# MonitorWizard-Logger.net
KiCad netlist of a schematic drawn in EAGLE
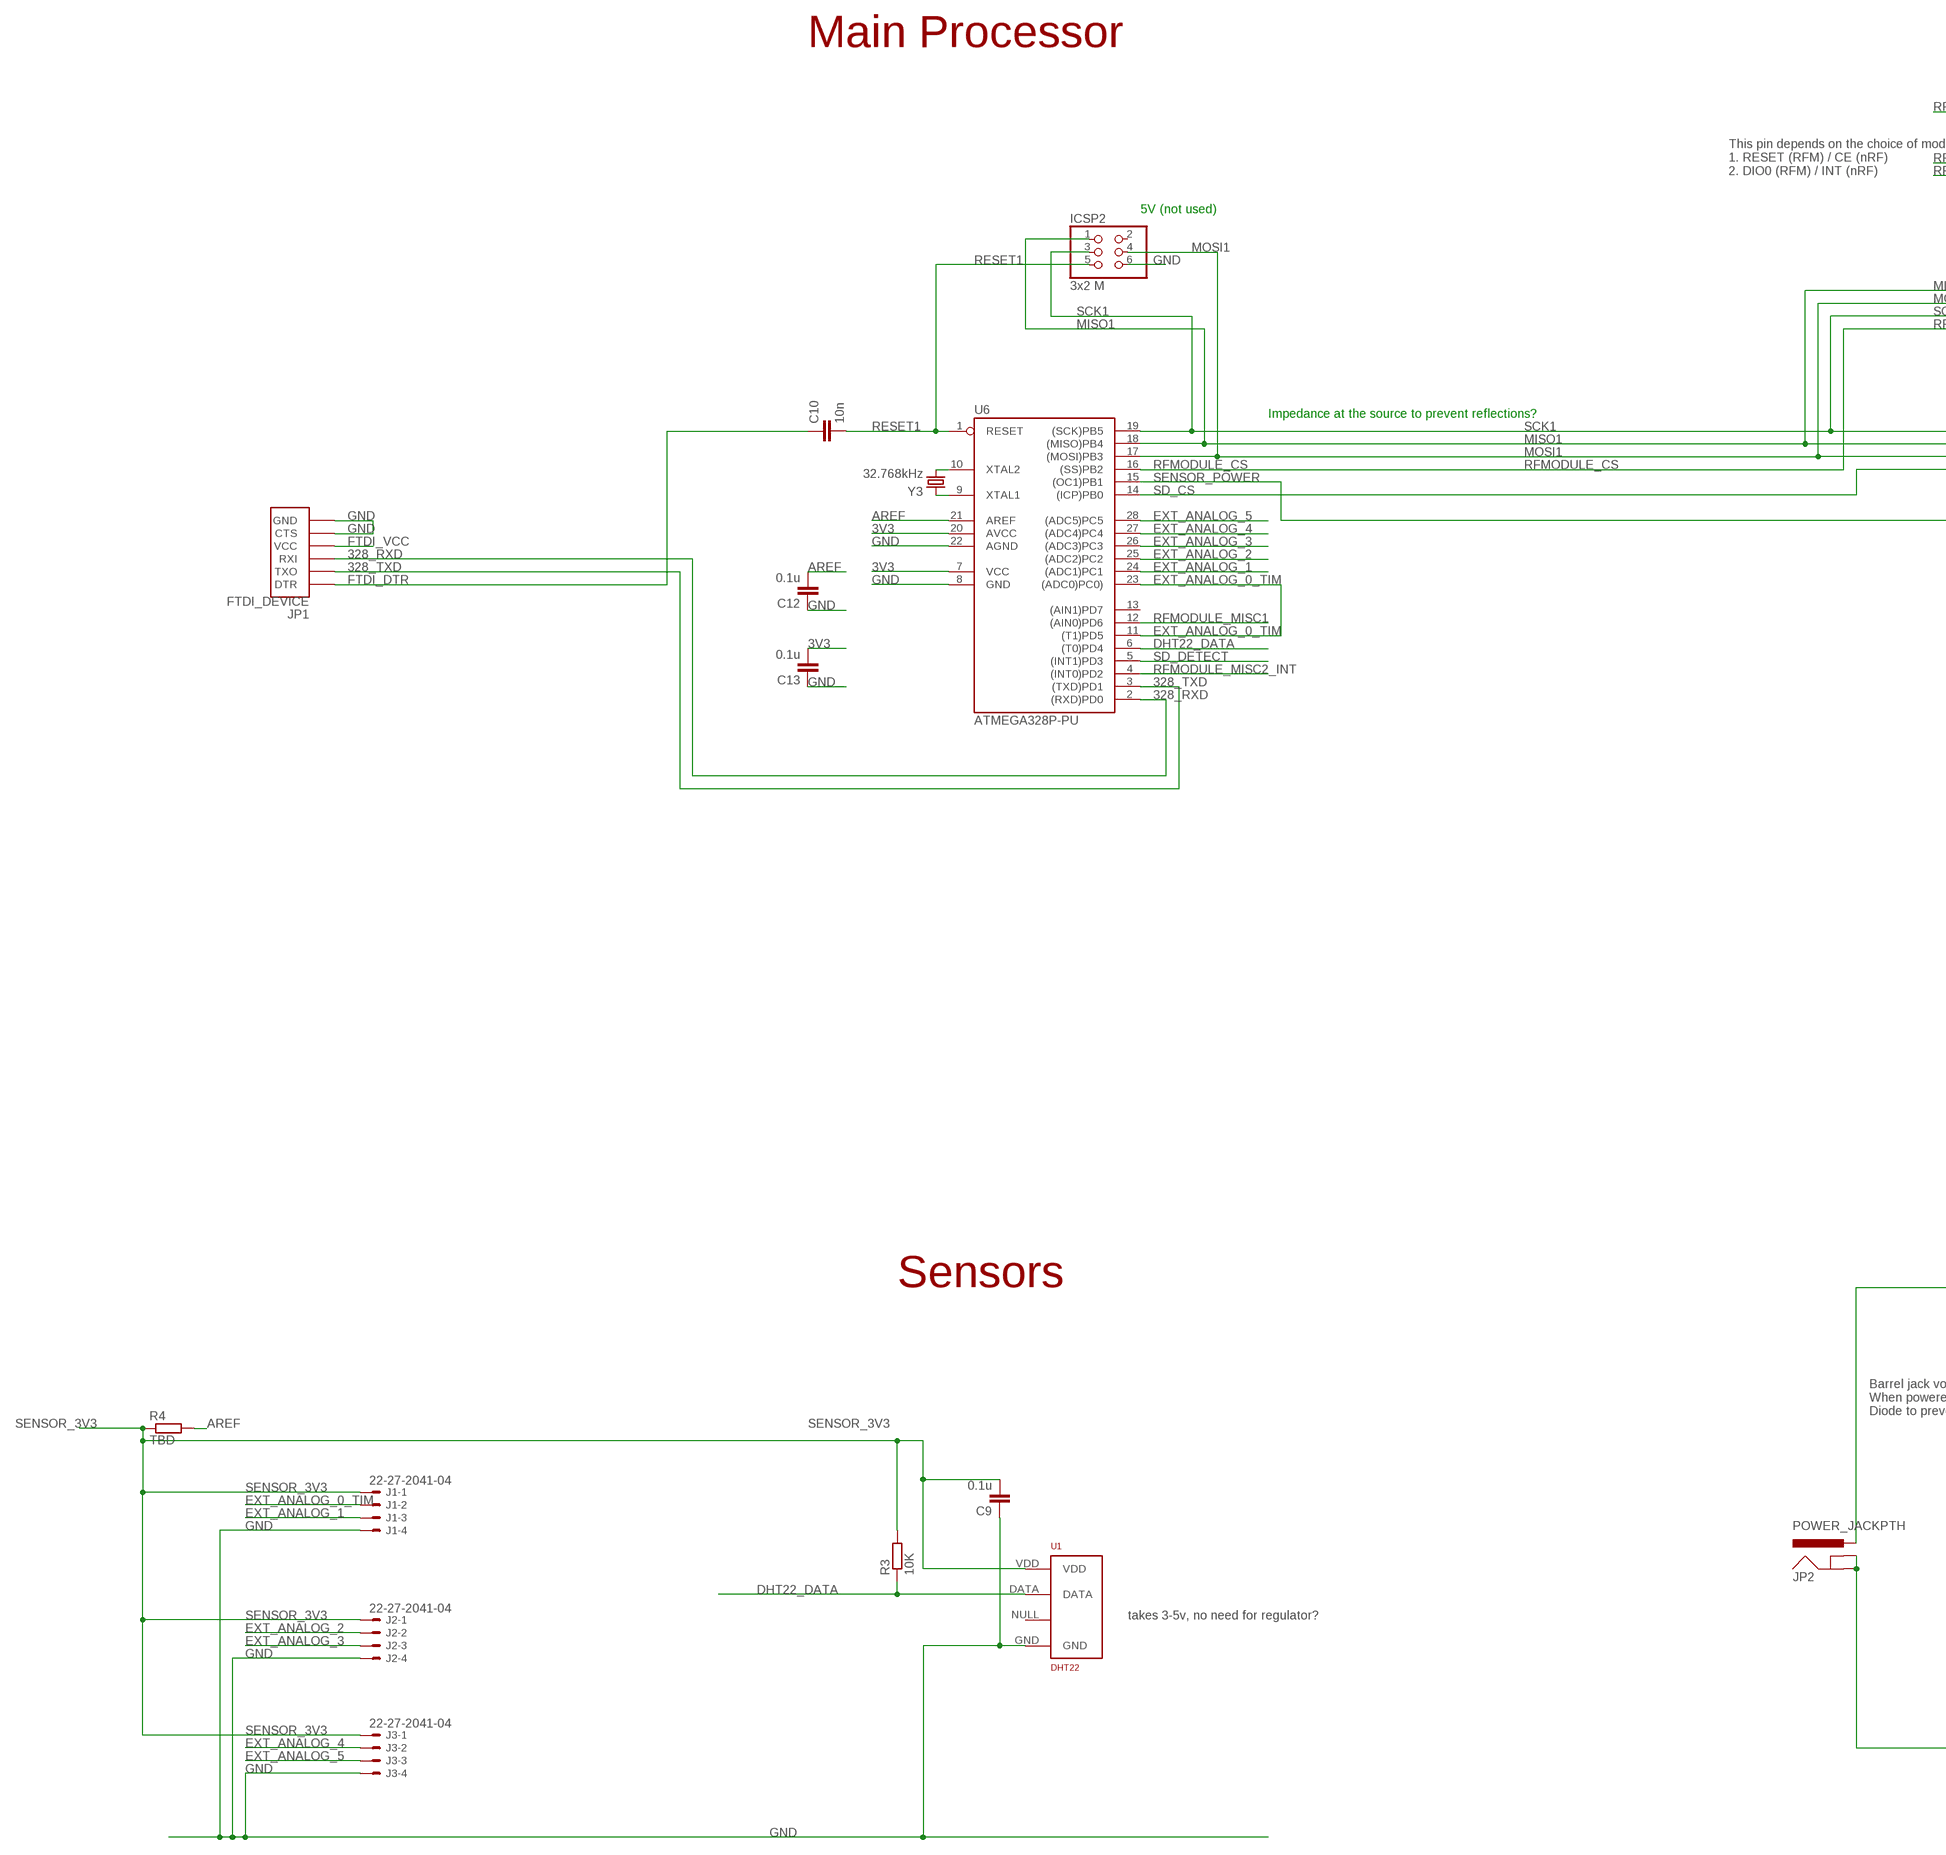
[diagram p0: schematic, sheet 1, part 1 of 2]
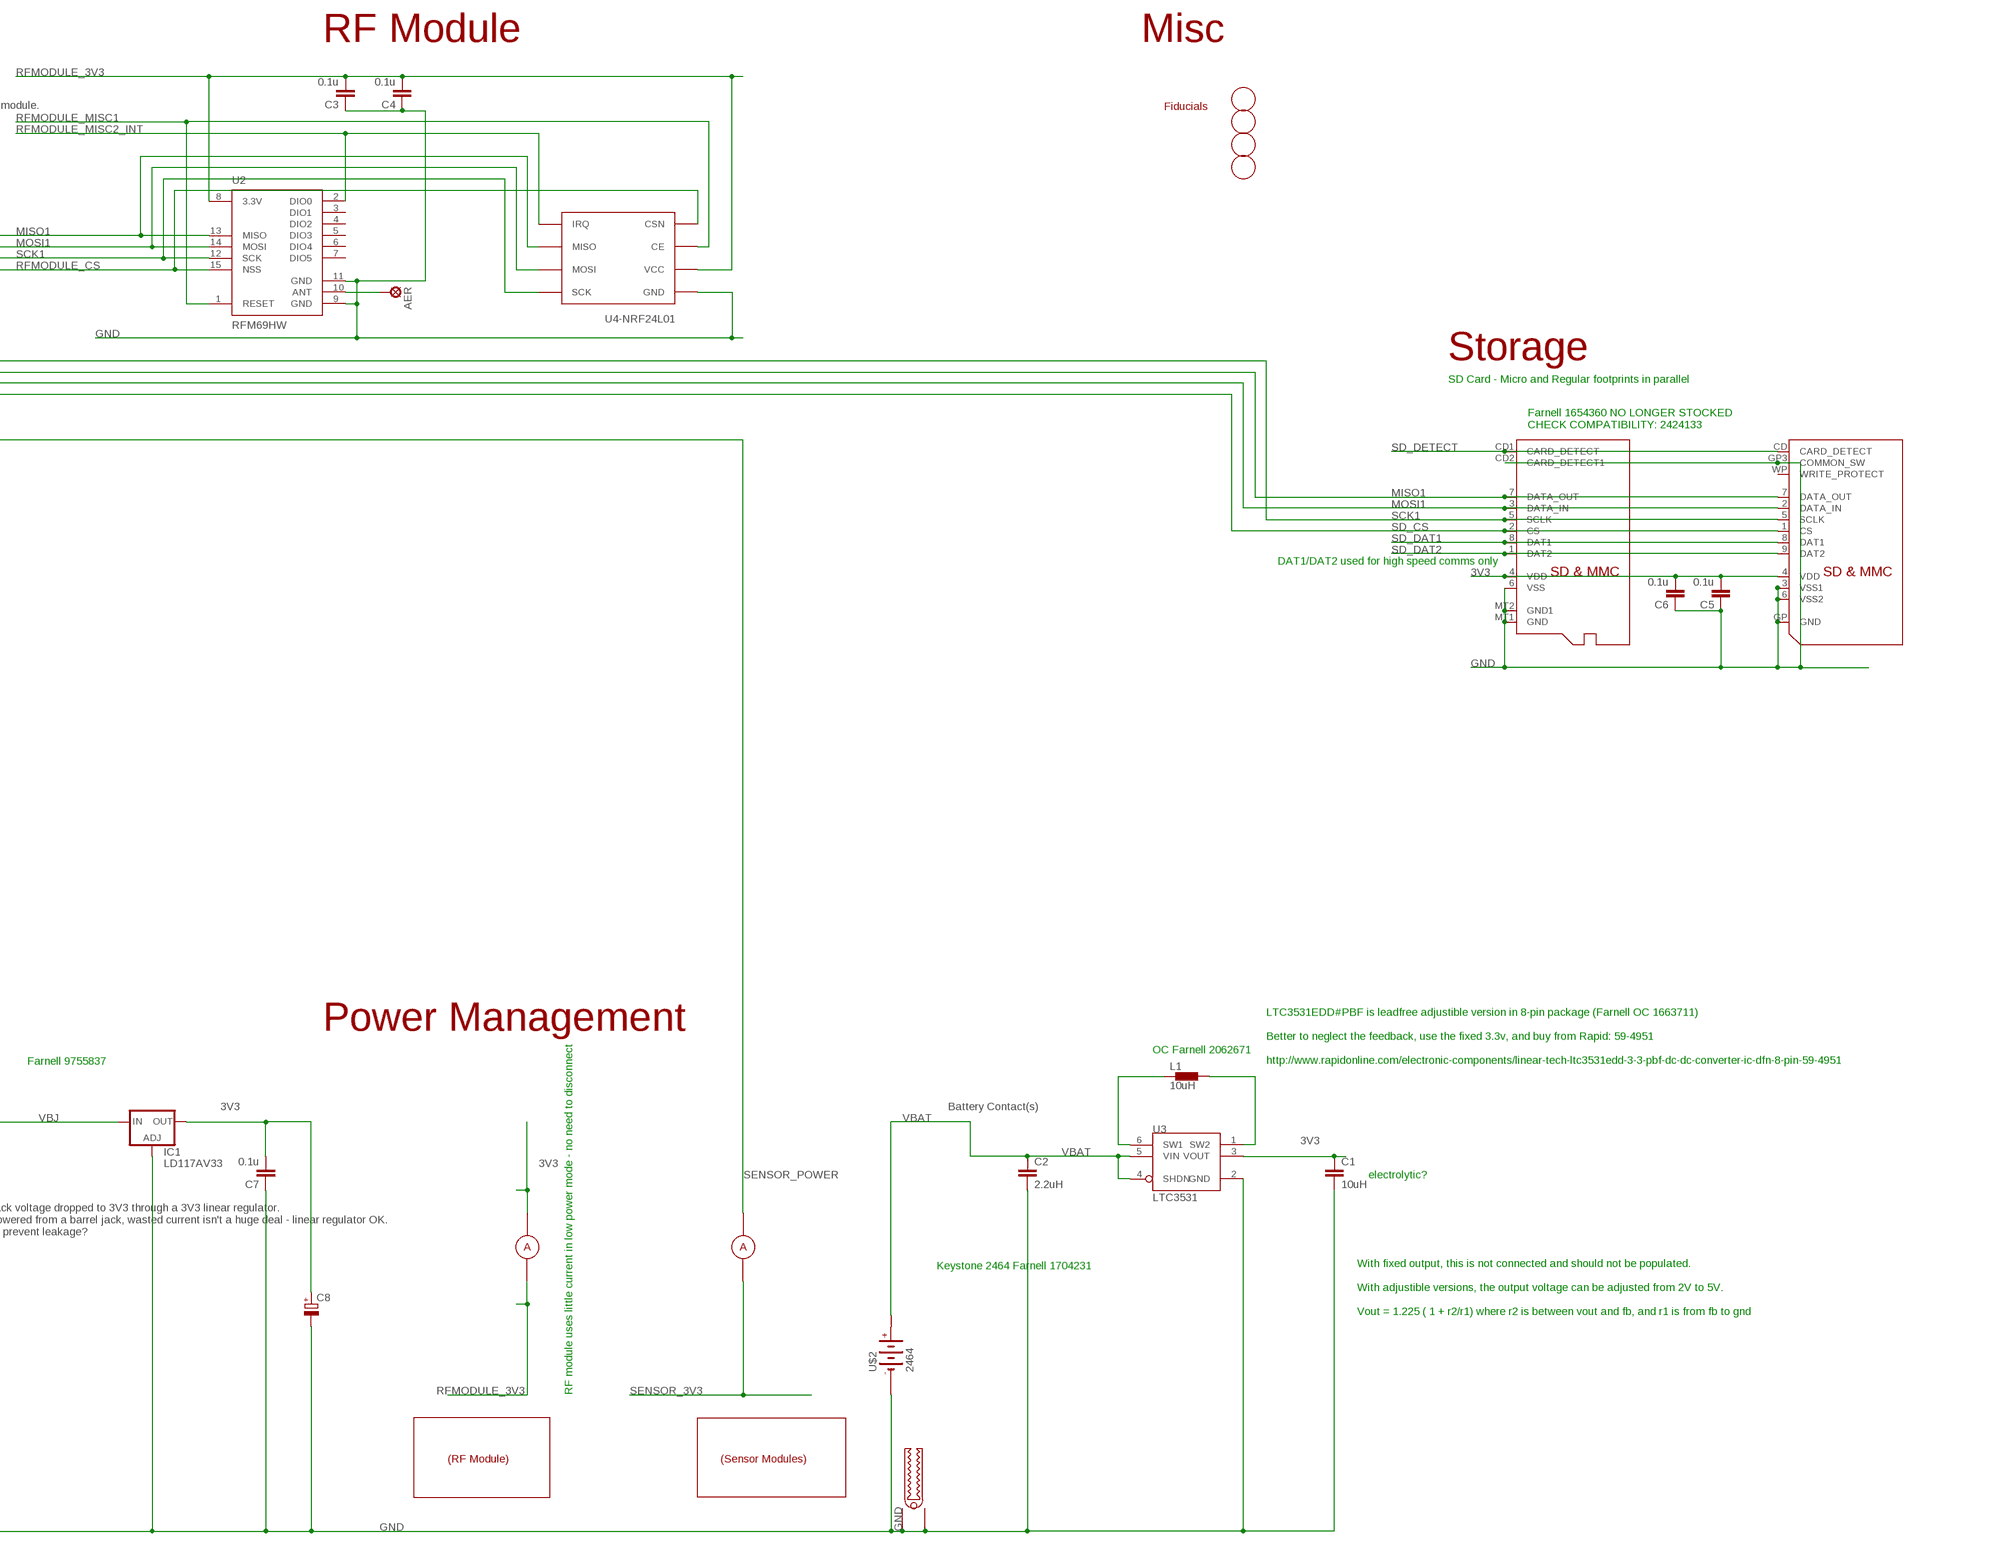
[diagram p1: schematic, sheet 1, part 2 of 2]

(export (version "E")
  (design (tool "Eeschema 10.0.6"))
  (components
    (comp (ref "AER")
      (value "LSP10")
      (footprint "eagle-import:LSP10")
      (libsource (lib "eagle-import") (part "LSP10"))
    )
    (comp (ref "C1")
      (value "10uH")
      (footprint "eagle-import:C025-024X044")
      (libsource (lib "eagle-import") (part "C-EU025-024X044"))
    )
    (comp (ref "C2")
      (value "2.2uH")
      (footprint "eagle-import:C025-024X044")
      (libsource (lib "eagle-import") (part "C-EU025-024X044"))
    )
    (comp (ref "C3")
      (value "0.1u")
      (footprint "eagle-import:C025-024X044")
      (libsource (lib "eagle-import") (part "C-EU025-024X044"))
    )
    (comp (ref "C4")
      (value "0.1u")
      (footprint "eagle-import:C025-024X044")
      (libsource (lib "eagle-import") (part "C-EU025-024X044"))
    )
    (comp (ref "C5")
      (value "0.1u")
      (footprint "eagle-import:C025-024X044")
      (libsource (lib "eagle-import") (part "C-EU025-024X044"))
    )
    (comp (ref "C6")
      (value "0.1u")
      (footprint "eagle-import:C025-024X044")
      (libsource (lib "eagle-import") (part "C-EU025-024X044"))
    )
    (comp (ref "C7")
      (value "0.1u")
      (footprint "eagle-import:C025-024X044")
      (libsource (lib "eagle-import") (part "C-EU025-024X044"))
    )
    (comp (ref "C8")
      (value "CPOL-EUE2.5-6")
      (footprint "eagle-import:E2,5-6")
      (libsource (lib "eagle-import") (part "CPOL-EUE2.5-6"))
    )
    (comp (ref "C9")
      (value "0.1u")
      (footprint "eagle-import:C025-024X044")
      (libsource (lib "eagle-import") (part "C-EU025-024X044"))
    )
    (comp (ref "C10")
      (value "10n")
      (footprint "eagle-import:C025-024X044")
      (libsource (lib "eagle-import") (part "C-EU025-024X044"))
    )
    (comp (ref "C12")
      (value "0.1u")
      (footprint "eagle-import:C025-024X044")
      (libsource (lib "eagle-import") (part "C-EU025-024X044"))
    )
    (comp (ref "C13")
      (value "0.1u")
      (footprint "eagle-import:C025-024X044")
      (libsource (lib "eagle-import") (part "C-EU025-024X044"))
    )
    (comp (ref "CON1")
      (value "MICROSD")
      (footprint "eagle-import:MICROSD")
      (libsource (lib "eagle-import") (part "MICROSD"))
    )
    (comp (ref "FD1")
      (value "FIDUCIALMOUNT")
      (footprint "eagle-import:FIDUCIA-MOUNT")
      (libsource (lib "eagle-import") (part "FIDUCIALMOUNT"))
    )
    (comp (ref "FD2")
      (value "FIDUCIALMOUNT")
      (footprint "eagle-import:FIDUCIA-MOUNT")
      (libsource (lib "eagle-import") (part "FIDUCIALMOUNT"))
    )
    (comp (ref "FD3")
      (value "FIDUCIALMOUNT")
      (footprint "eagle-import:FIDUCIA-MOUNT")
      (libsource (lib "eagle-import") (part "FIDUCIALMOUNT"))
    )
    (comp (ref "FD4")
      (value "FIDUCIALMOUNT")
      (footprint "eagle-import:FIDUCIA-MOUNT")
      (libsource (lib "eagle-import") (part "FIDUCIALMOUNT"))
    )
    (comp (ref "GND")
      (value "ALLIGATOR")
      (footprint "eagle-import:ALLIGATOR")
      (libsource (lib "eagle-import") (part "ALLIGATOR"))
    )
    (comp (ref "IC1")
      (value "LD117AV33")
      (footprint "eagle-import:TO220L1")
      (libsource (lib "eagle-import") (part "LD117A?V33"))
    )
    (comp (ref "ICSP2")
      (value "3x2 M")
      (footprint "eagle-import:2X03")
      (libsource (lib "eagle-import") (part "PINHD-2X3"))
    )
    (comp (ref "I_RF")
      (value "CURRENT_MEASURE_0.4A")
      (footprint "eagle-import:CURRENT_MEASURE")
      (libsource (lib "eagle-import") (part "CURRENT_MEASURE_0.4A"))
    )
    (comp (ref "I_SENSE")
      (value "CURRENT_MEASURE_0.4A")
      (footprint "eagle-import:CURRENT_MEASURE")
      (libsource (lib "eagle-import") (part "CURRENT_MEASURE_0.4A"))
    )
    (comp (ref "J1")
      (value "22-27-2041-04")
      (footprint "eagle-import:6410-04")
      (libsource (lib "eagle-import") (part "22-?-0427-2041"))
    )
    (comp (ref "J2")
      (value "22-27-2041-04")
      (footprint "eagle-import:6410-04")
      (libsource (lib "eagle-import") (part "22-?-0427-2041"))
    )
    (comp (ref "J3")
      (value "22-27-2041-04")
      (footprint "eagle-import:6410-04")
      (libsource (lib "eagle-import") (part "22-?-0427-2041"))
    )
    (comp (ref "JP1")
      (value "FTDI_DEVICE")
      (footprint "eagle-import:FTDI_DEVICE_SIDE")
      (libsource (lib "eagle-import") (part "FTDI_DEVICE"))
    )
    (comp (ref "JP2")
      (value "POWER_JACKPTH")
      (footprint "eagle-import:POWER_JACK_PTH")
      (libsource (lib "eagle-import") (part "POWER_JACKPTH"))
    )
    (comp (ref "L1")
      (value "10uH")
      (footprint "eagle-import:L-RADIAL-2-5OD")
      (libsource (lib "eagle-import") (part "MURATA-1100R"))
    )
    (comp (ref "R3")
      (value "10K")
      (footprint "eagle-import:0207_10")
      (libsource (lib "eagle-import") (part "R-EU_0207/10"))
    )
    (comp (ref "R4")
      (value "TBD")
      (footprint "eagle-import:0207_10")
      (libsource (lib "eagle-import") (part "R-EU_0207/10"))
    )
    (comp (ref "U$1")
      (value "SDMMC06132")
      (footprint "eagle-import:06132")
      (libsource (lib "eagle-import") (part "SDMMC06132"))
    )
    (comp (ref "U$2")
      (value "2464")
      (footprint "eagle-import:2464")
      (libsource (lib "eagle-import") (part "2464"))
    )
    (comp (ref "U1")
      (value "DHT22")
      (footprint "eagle-import:RHT03_DHT-22")
      (libsource (lib "eagle-import") (part "RHT03_DHT-22_AM2302"))
    )
    (comp (ref "U2")
      (value "RFM69HW")
      (footprint "eagle-import:RFM69W-XXXS2")
      (libsource (lib "eagle-import") (part "RFM69HW"))
    )
    (comp (ref "U3")
      (value "LTC3531")
      (footprint "eagle-import:TSOT23-6")
      (libsource (lib "eagle-import") (part "LTC3531"))
    )
    (comp (ref "U4-NRF24L01")
      (value "NRF24L01+-PCB-AERIAL")
      (footprint "eagle-import:NRF24L01-PCB-AERIAL")
      (libsource (lib "eagle-import") (part "NRF24L01+-PCB-AERIAL"))
    )
    (comp (ref "U6")
      (value "ATMEGA328P-PU")
      (footprint "eagle-import:DIL28-3")
      (libsource (lib "eagle-import") (part "ATMEGA328P-PU"))
    )
    (comp (ref "Y3")
      (value "32.768kHz")
      (footprint "eagle-import:TC26HEZ")
      (libsource (lib "eagle-import") (part "CRYSTALTC26H_EZ"))
    )
  )
  (nets
    (net (code "1") (name "/3V3") (class "Default")
      (node (ref "C1") (pin "1") (pinfunction "1_1") (pintype "passive"))
      (node (ref "C13") (pin "2") (pinfunction "2_2") (pintype "passive"))
      (node (ref "C5") (pin "2") (pinfunction "2_2") (pintype "passive"))
      (node (ref "C6") (pin "2") (pinfunction "2_2") (pintype "passive"))
      (node (ref "C7") (pin "2") (pinfunction "2_2") (pintype "passive"))
      (node (ref "C8") (pin "+") (pinfunction "+_+") (pintype "passive"))
      (node (ref "CON1") (pin "4") (pinfunction "VDD_4") (pintype "power_in"))
      (node (ref "IC1") (pin "2") (pinfunction "OUT_2") (pintype "passive"))
      (node (ref "I_RF") (pin "P$1") (pinfunction "P$1_P$1") (pintype "bidirectional"))
      (node (ref "U$1") (pin "4") (pinfunction "VDD_4") (pintype "power_in"))
      (node (ref "U3") (pin "3") (pinfunction "VOUT_3") (pintype "bidirectional"))
      (node (ref "U6") (pin "20") (pinfunction "AVCC_20") (pintype "power_in"))
      (node (ref "U6") (pin "7") (pinfunction "VCC_7") (pintype "power_in"))
    )
    (net (code "2") (name "/328_RXD") (class "Default")
      (node (ref "JP1") (pin "P$3") (pinfunction "RXI_P$3") (pintype "bidirectional"))
      (node (ref "U6") (pin "2") (pinfunction "(RXD)PD0_2") (pintype "bidirectional"))
    )
    (net (code "3") (name "/328_TXD") (class "Default")
      (node (ref "JP1") (pin "P$2") (pinfunction "TXO_P$2") (pintype "bidirectional"))
      (node (ref "U6") (pin "3") (pinfunction "(TXD)PD1_3") (pintype "bidirectional"))
    )
    (net (code "4") (name "/AREF") (class "Default")
      (node (ref "C12") (pin "2") (pinfunction "2_2") (pintype "passive"))
      (node (ref "R4") (pin "2") (pinfunction "2_2") (pintype "passive"))
      (node (ref "U6") (pin "21") (pinfunction "AREF_21") (pintype "passive"))
    )
    (net (code "5") (name "/DHT22_DATA") (class "Default")
      (node (ref "R3") (pin "1") (pinfunction "1_1") (pintype "passive"))
      (node (ref "U1") (pin "DATA") (pinfunction "DATA_DATA") (pintype "bidirectional"))
      (node (ref "U6") (pin "6") (pinfunction "(T0)PD4_6") (pintype "bidirectional"))
    )
    (net (code "6") (name "/EXT_ANALOG_0_TIM") (class "Default")
      (node (ref "J1") (pin "2") (pinfunction "S_2") (pintype "passive"))
      (node (ref "U6") (pin "11") (pinfunction "(T1)PD5_11") (pintype "bidirectional"))
      (node (ref "U6") (pin "23") (pinfunction "(ADC0)PC0)_23") (pintype "bidirectional"))
    )
    (net (code "7") (name "/EXT_ANALOG_1") (class "Default")
      (node (ref "J1") (pin "3") (pinfunction "S_3") (pintype "passive"))
      (node (ref "U6") (pin "24") (pinfunction "(ADC1)PC1_24") (pintype "bidirectional"))
    )
    (net (code "8") (name "/EXT_ANALOG_2") (class "Default")
      (node (ref "J2") (pin "2") (pinfunction "S_2") (pintype "passive"))
      (node (ref "U6") (pin "25") (pinfunction "(ADC2)PC2_25") (pintype "bidirectional"))
    )
    (net (code "9") (name "/EXT_ANALOG_3") (class "Default")
      (node (ref "J2") (pin "3") (pinfunction "S_3") (pintype "passive"))
      (node (ref "U6") (pin "26") (pinfunction "(ADC3)PC3_26") (pintype "bidirectional"))
    )
    (net (code "10") (name "/EXT_ANALOG_4") (class "Default")
      (node (ref "J3") (pin "2") (pinfunction "S_2") (pintype "passive"))
      (node (ref "U6") (pin "27") (pinfunction "(ADC4)PC4_27") (pintype "bidirectional"))
    )
    (net (code "11") (name "/EXT_ANALOG_5") (class "Default")
      (node (ref "J3") (pin "3") (pinfunction "S_3") (pintype "passive"))
      (node (ref "U6") (pin "28") (pinfunction "(ADC5)PC5_28") (pintype "bidirectional"))
    )
    (net (code "12") (name "/FTDI_DTR") (class "Default")
      (node (ref "C10") (pin "1") (pinfunction "1_1") (pintype "passive"))
      (node (ref "JP1") (pin "P$1") (pinfunction "DTR_P$1") (pintype "bidirectional"))
    )
    (net (code "13") (name "/FTDI_VCC") (class "Default")
      (node (ref "JP1") (pin "P$4") (pinfunction "VCC_P$4") (pintype "bidirectional"))
    )
    (net (code "14") (name "/GND") (class "Default")
      (node (ref "C1") (pin "2") (pinfunction "2_2") (pintype "passive"))
      (node (ref "C12") (pin "1") (pinfunction "1_1") (pintype "passive"))
      (node (ref "C13") (pin "1") (pinfunction "1_1") (pintype "passive"))
      (node (ref "C2") (pin "2") (pinfunction "2_2") (pintype "passive"))
      (node (ref "C3") (pin "1") (pinfunction "1_1") (pintype "passive"))
      (node (ref "C4") (pin "1") (pinfunction "1_1") (pintype "passive"))
      (node (ref "C5") (pin "1") (pinfunction "1_1") (pintype "passive"))
      (node (ref "C6") (pin "1") (pinfunction "1_1") (pintype "passive"))
      (node (ref "C7") (pin "1") (pinfunction "1_1") (pintype "passive"))
      (node (ref "C8") (pin "-") (pinfunction "-_-") (pintype "passive"))
      (node (ref "C9") (pin "1") (pinfunction "1_1") (pintype "passive"))
      (node (ref "CON1") (pin "6") (pinfunction "VSS_6") (pintype "power_in"))
      (node (ref "CON1") (pin "CD2") (pinfunction "CARD_DETECT1_CD2") (pintype "passive"))
      (node (ref "CON1") (pin "MT1") (pinfunction "GND_MT1") (pintype "power_in"))
      (node (ref "CON1") (pin "MT2") (pinfunction "GND1_MT2") (pintype "power_in"))
      (node (ref "GND") (pin "BTM") (pinfunction "BTM_BTM") (pintype "bidirectional"))
      (node (ref "GND") (pin "TOP") (pinfunction "TOP_TOP") (pintype "bidirectional"))
      (node (ref "IC1") (pin "1") (pinfunction "ADJ_1") (pintype "input"))
      (node (ref "ICSP2") (pin "6") (pinfunction "6_6") (pintype "passive"))
      (node (ref "J1") (pin "4") (pinfunction "S_4") (pintype "passive"))
      (node (ref "J2") (pin "4") (pinfunction "S_4") (pintype "passive"))
      (node (ref "J3") (pin "4") (pinfunction "S_4") (pintype "passive"))
      (node (ref "JP1") (pin "P$5") (pinfunction "CTS_P$5") (pintype "bidirectional"))
      (node (ref "JP1") (pin "P$6") (pinfunction "GND_P$6") (pintype "bidirectional"))
      (node (ref "JP2") (pin "GND") (pinfunction "GND_GND") (pintype "bidirectional"))
      (node (ref "JP2") (pin "GNDBREAK") (pinfunction "GNDBREAK_GNDBREAK") (pintype "bidirectional"))
      (node (ref "U$1") (pin "3") (pinfunction "VSS1_3") (pintype "power_in"))
      (node (ref "U$1") (pin "6") (pinfunction "VSS2_6") (pintype "power_in"))
      (node (ref "U$1") (pin "GP") (pinfunction "GND_GP") (pintype "power_in"))
      (node (ref "U$1") (pin "GP3") (pinfunction "COMMON_SW_GP3") (pintype "passive"))
      (node (ref "U$2") (pin "-") (pinfunction "-_-") (pintype "passive"))
      (node (ref "U1") (pin "GND") (pinfunction "GND_GND") (pintype "power_in"))
      (node (ref "U2") (pin "11") (pinfunction "GND_11") (pintype "power_in"))
      (node (ref "U2") (pin "9") (pinfunction "GND_9") (pintype "power_in"))
      (node (ref "U3") (pin "2") (pinfunction "GND_2") (pintype "bidirectional"))
      (node (ref "U4-NRF24L01") (pin "P$1") (pinfunction "GND_P$1") (pintype "power_in"))
      (node (ref "U6") (pin "22") (pinfunction "AGND_22") (pintype "power_in"))
      (node (ref "U6") (pin "8") (pinfunction "GND_8") (pintype "power_in"))
    )
    (net (code "15") (name "/MISO1") (class "Default")
      (node (ref "CON1") (pin "7") (pinfunction "DATA_OUT_7") (pintype "output"))
      (node (ref "ICSP2") (pin "1") (pinfunction "1_1") (pintype "passive"))
      (node (ref "U$1") (pin "7") (pinfunction "DATA_OUT_7") (pintype "output"))
      (node (ref "U2") (pin "13") (pinfunction "MISO_13") (pintype "bidirectional"))
      (node (ref "U4-NRF24L01") (pin "P$7") (pinfunction "MISO_P$7") (pintype "bidirectional"))
      (node (ref "U6") (pin "18") (pinfunction "(MISO)PB4_18") (pintype "bidirectional"))
    )
    (net (code "16") (name "/MOSI1") (class "Default")
      (node (ref "CON1") (pin "3") (pinfunction "DATA_IN_3") (pintype "input"))
      (node (ref "ICSP2") (pin "4") (pinfunction "4_4") (pintype "passive"))
      (node (ref "U$1") (pin "2") (pinfunction "DATA_IN_2") (pintype "input"))
      (node (ref "U2") (pin "14") (pinfunction "MOSI_14") (pintype "input"))
      (node (ref "U4-NRF24L01") (pin "P$6") (pinfunction "MOSI_P$6") (pintype "bidirectional"))
      (node (ref "U6") (pin "17") (pinfunction "(MOSI)PB3_17") (pintype "bidirectional"))
    )
    (net (code "17") (name "/RESET1") (class "Default")
      (node (ref "C10") (pin "2") (pinfunction "2_2") (pintype "passive"))
      (node (ref "ICSP2") (pin "5") (pinfunction "5_5") (pintype "passive"))
      (node (ref "U6") (pin "1") (pinfunction "RESET_1") (pintype "input"))
    )
    (net (code "18") (name "/RFMODULE_3V3") (class "Default")
      (node (ref "C3") (pin "2") (pinfunction "2_2") (pintype "passive"))
      (node (ref "C4") (pin "2") (pinfunction "2_2") (pintype "passive"))
      (node (ref "I_RF") (pin "P$2") (pinfunction "P$2_P$2") (pintype "bidirectional"))
      (node (ref "U2") (pin "8") (pinfunction "3.3V_8") (pintype "power_in"))
      (node (ref "U4-NRF24L01") (pin "P$2") (pinfunction "VCC_P$2") (pintype "power_in"))
    )
    (net (code "19") (name "/RFMODULE_CS") (class "Default")
      (node (ref "U2") (pin "15") (pinfunction "NSS_15") (pintype "input"))
      (node (ref "U4-NRF24L01") (pin "P$4") (pinfunction "CSN_P$4") (pintype "bidirectional"))
      (node (ref "U6") (pin "16") (pinfunction "(SS)PB2_16") (pintype "bidirectional"))
    )
    (net (code "20") (name "/RFMODULE_MISC1") (class "Default")
      (node (ref "U2") (pin "1") (pinfunction "RESET_1") (pintype "input"))
      (node (ref "U4-NRF24L01") (pin "P$3") (pinfunction "CE_P$3") (pintype "bidirectional"))
      (node (ref "U6") (pin "12") (pinfunction "(AIN0)PD6_12") (pintype "bidirectional"))
    )
    (net (code "21") (name "/RFMODULE_MISC2_INT") (class "Default")
      (node (ref "U2") (pin "2") (pinfunction "DIO0_2") (pintype "bidirectional"))
      (node (ref "U4-NRF24L01") (pin "P$8") (pinfunction "IRQ_P$8") (pintype "bidirectional"))
      (node (ref "U6") (pin "4") (pinfunction "(INT0)PD2_4") (pintype "bidirectional"))
    )
    (net (code "22") (name "/SCK1") (class "Default")
      (node (ref "CON1") (pin "5") (pinfunction "SCLK_5") (pintype "input"))
      (node (ref "ICSP2") (pin "3") (pinfunction "3_3") (pintype "passive"))
      (node (ref "U$1") (pin "5") (pinfunction "SCLK_5") (pintype "input"))
      (node (ref "U2") (pin "12") (pinfunction "SCK_12") (pintype "input"))
      (node (ref "U4-NRF24L01") (pin "P$5") (pinfunction "SCK_P$5") (pintype "bidirectional"))
      (node (ref "U6") (pin "19") (pinfunction "(SCK)PB5_19") (pintype "bidirectional"))
    )
    (net (code "23") (name "/SD_CS") (class "Default")
      (node (ref "CON1") (pin "2") (pinfunction "CS_2") (pintype "input"))
      (node (ref "U$1") (pin "1") (pinfunction "CS_1") (pintype "input"))
      (node (ref "U6") (pin "14") (pinfunction "(ICP)PB0_14") (pintype "bidirectional"))
    )
    (net (code "24") (name "/SD_DAT1") (class "Default")
      (node (ref "CON1") (pin "8") (pinfunction "DAT1_8") (pintype "bidirectional"))
      (node (ref "U$1") (pin "8") (pinfunction "DAT1_8") (pintype "bidirectional"))
    )
    (net (code "25") (name "/SD_DAT2") (class "Default")
      (node (ref "CON1") (pin "1") (pinfunction "DAT2_1") (pintype "bidirectional"))
      (node (ref "U$1") (pin "9") (pinfunction "DAT2_9") (pintype "bidirectional"))
    )
    (net (code "26") (name "/SD_DETECT") (class "Default")
      (node (ref "CON1") (pin "CD1") (pinfunction "CARD_DETECT_CD1") (pintype "passive"))
      (node (ref "U$1") (pin "CD") (pinfunction "CARD_DETECT_CD") (pintype "passive"))
      (node (ref "U6") (pin "5") (pinfunction "(INT1)PD3_5") (pintype "bidirectional"))
    )
    (net (code "27") (name "/SENSOR_3V3") (class "Default")
      (node (ref "C9") (pin "2") (pinfunction "2_2") (pintype "passive"))
      (node (ref "I_SENSE") (pin "P$2") (pinfunction "P$2_P$2") (pintype "bidirectional"))
      (node (ref "J1") (pin "1") (pinfunction "S_1") (pintype "passive"))
      (node (ref "J2") (pin "1") (pinfunction "S_1") (pintype "passive"))
      (node (ref "J3") (pin "1") (pinfunction "S_1") (pintype "passive"))
      (node (ref "R3") (pin "2") (pinfunction "2_2") (pintype "passive"))
      (node (ref "R4") (pin "1") (pinfunction "1_1") (pintype "passive"))
      (node (ref "U1") (pin "VDD") (pinfunction "VDD_VDD") (pintype "power_in"))
    )
    (net (code "28") (name "/SENSOR_POWER") (class "Default")
      (node (ref "I_SENSE") (pin "P$1") (pinfunction "P$1_P$1") (pintype "bidirectional"))
      (node (ref "U6") (pin "15") (pinfunction "(OC1)PB1_15") (pintype "bidirectional"))
    )
    (net (code "29") (name "/VBAT") (class "Default")
      (node (ref "C2") (pin "1") (pinfunction "1_1") (pintype "passive"))
      (node (ref "U$2") (pin "+") (pinfunction "+_+") (pintype "passive"))
      (node (ref "U3") (pin "4") (pinfunction "SHDN_4") (pintype "bidirectional"))
      (node (ref "U3") (pin "5") (pinfunction "VIN_5") (pintype "bidirectional"))
    )
    (net (code "30") (name "/VBJ") (class "Default")
      (node (ref "IC1") (pin "3") (pinfunction "IN_3") (pintype "input"))
      (node (ref "JP2") (pin "PWR") (pinfunction "PWR_PWR") (pintype "bidirectional"))
    )
    (net (code "31") (name "Net-(L1-1)") (class "Default")
      (node (ref "L1") (pin "P$1") (pinfunction "1_P$1") (pintype "passive"))
      (node (ref "U3") (pin "6") (pinfunction "SW1_6") (pintype "bidirectional"))
    )
    (net (code "32") (name "Net-(L1-2)") (class "Default")
      (node (ref "L1") (pin "P$2") (pinfunction "2_P$2") (pintype "passive"))
      (node (ref "U3") (pin "1") (pinfunction "SW2_1") (pintype "bidirectional"))
    )
    (net (code "33") (name "Net-(U2-ANT)") (class "Default")
      (node (ref "AER") (pin "MP") (pinfunction "MP_MP") (pintype "passive"))
      (node (ref "U2") (pin "10") (pinfunction "ANT_10") (pintype "passive"))
    )
    (net (code "34") (name "Net-(U6-XTAL1)") (class "Default")
      (node (ref "U6") (pin "9") (pinfunction "XTAL1_9") (pintype "bidirectional"))
      (node (ref "Y3") (pin "2") (pinfunction "2_2") (pintype "passive"))
    )
    (net (code "35") (name "Net-(U6-XTAL2)") (class "Default")
      (node (ref "U6") (pin "10") (pinfunction "XTAL2_10") (pintype "bidirectional"))
      (node (ref "Y3") (pin "1") (pinfunction "1_1") (pintype "passive"))
    )
    (net (code "36") (name "unconnected-(ICSP2-Pad2)") (class "Default")
      (node (ref "ICSP2") (pin "2") (pinfunction "2_2") (pintype "passive"))
    )
    (net (code "37") (name "unconnected-(U$1-WRITE_PROTECT-PadWP)") (class "Default")
      (node (ref "U$1") (pin "WP") (pinfunction "WRITE_PROTECT_WP") (pintype "passive"))
    )
    (net (code "38") (name "unconnected-(U1-PadNULL)") (class "Default")
      (node (ref "U1") (pin "NULL") (pinfunction "NULL_NULL") (pintype "no_connect"))
    )
    (net (code "39") (name "unconnected-(U2-DIO1-Pad3)") (class "Default")
      (node (ref "U2") (pin "3") (pinfunction "DIO1_3") (pintype "bidirectional"))
    )
    (net (code "40") (name "unconnected-(U2-DIO2-Pad4)") (class "Default")
      (node (ref "U2") (pin "4") (pinfunction "DIO2_4") (pintype "bidirectional"))
    )
    (net (code "41") (name "unconnected-(U2-DIO3-Pad5)") (class "Default")
      (node (ref "U2") (pin "5") (pinfunction "DIO3_5") (pintype "bidirectional"))
    )
    (net (code "42") (name "unconnected-(U2-DIO4-Pad6)") (class "Default")
      (node (ref "U2") (pin "6") (pinfunction "DIO4_6") (pintype "bidirectional"))
    )
    (net (code "43") (name "unconnected-(U2-DIO5-Pad7)") (class "Default")
      (node (ref "U2") (pin "7") (pinfunction "DIO5_7") (pintype "bidirectional"))
    )
    (net (code "44") (name "unconnected-(U6-(AIN1)PD7-Pad13)") (class "Default")
      (node (ref "U6") (pin "13") (pinfunction "(AIN1)PD7_13") (pintype "bidirectional"))
    )
  )
)
